# Peachy1-99-6-f.net
KiCad netlist of a schematic drawn in EAGLE
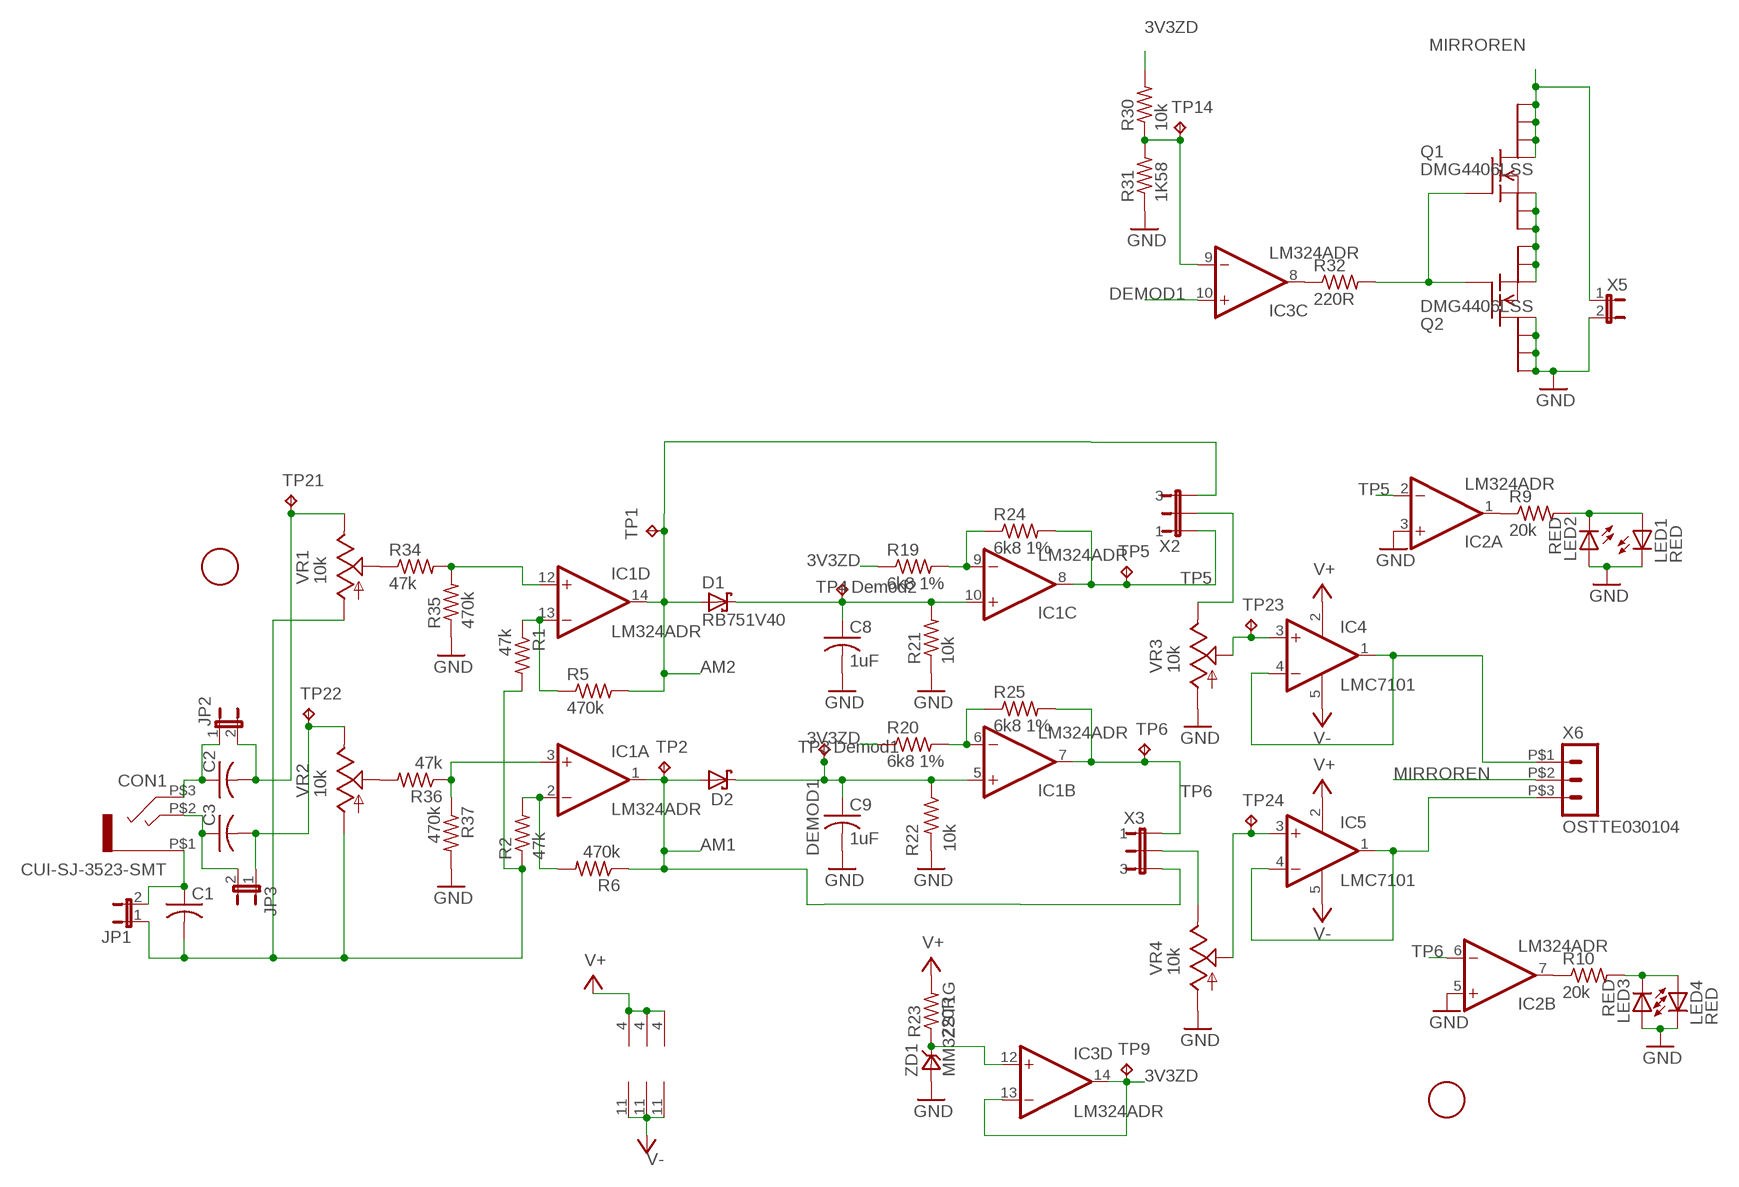
[diagram p0: schematic, sheet 1]
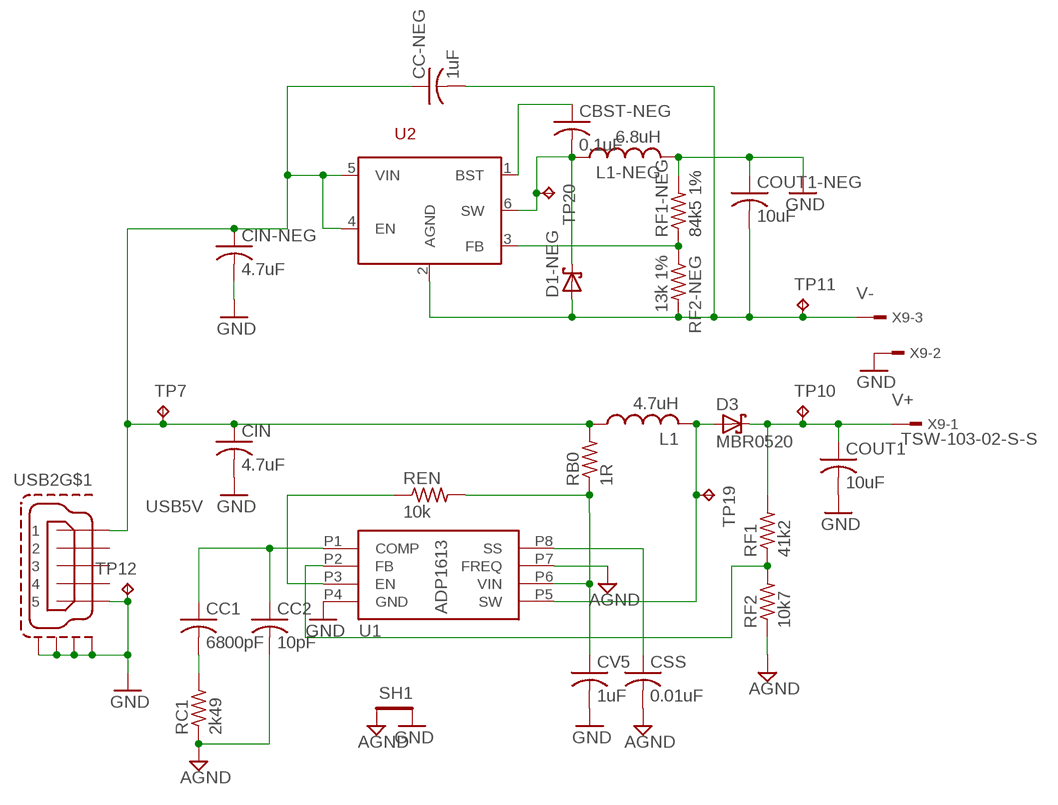
[diagram p1: schematic, sheet 2]
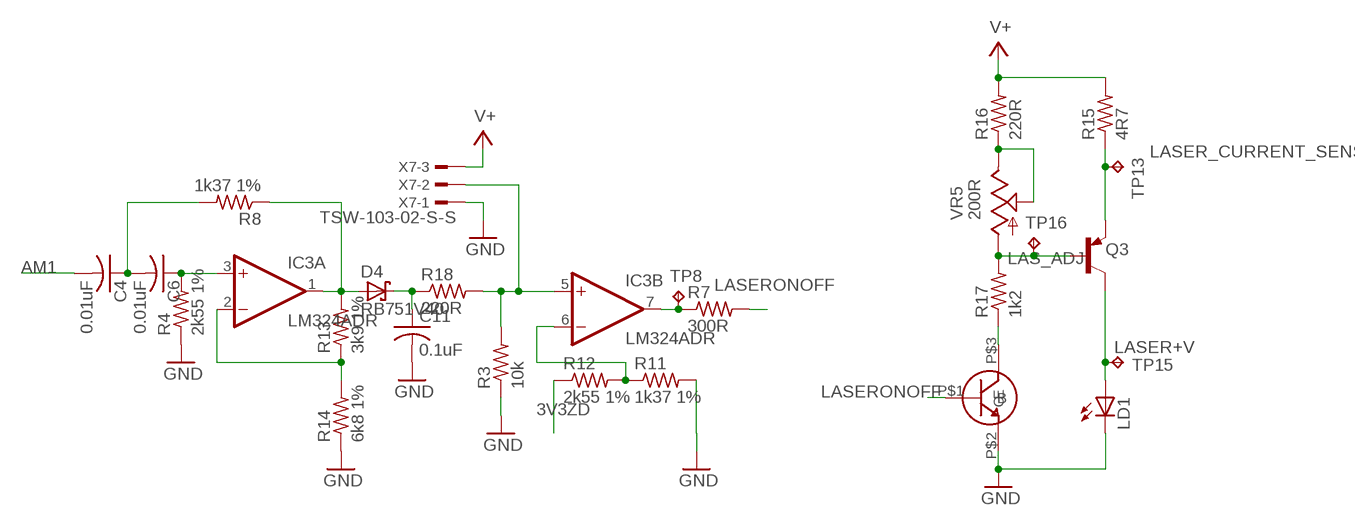
[diagram p2: schematic, sheet 3]
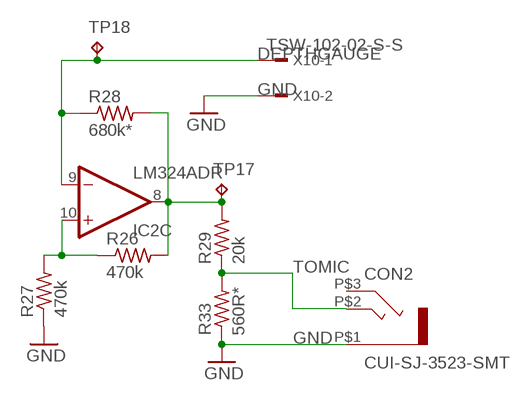
[diagram p3: schematic, sheet 4]

(export (version "E")
  (design (tool "Eeschema 10.0.6"))
  (components
    (comp (ref "C4")
      (value "0.01uF")
      (footprint "eagle-import:C0805")
      (fields (field (name "MPN") "CL21B103KBANNNC"))
      (libsource (lib "eagle-import") (part "C-US0805"))
    )
    (comp (ref "C6")
      (value "0.01uF")
      (footprint "eagle-import:C0805")
      (fields (field (name "MPN") "CL21B103KBANNNC"))
      (libsource (lib "eagle-import") (part "C-US0805"))
    )
    (comp (ref "C11")
      (value "0.1uF")
      (footprint "eagle-import:C0805")
      (fields (field (name "MPN") "CL21B104KACNNNC"))
      (libsource (lib "eagle-import") (part "C-US0805"))
    )
    (comp (ref "D4")
      (value "RB751V40")
      (footprint "eagle-import:SOD323-R")
      (fields (field (name "MPN") "RB751V40,115"))
      (libsource (lib "eagle-import") (part "RB751V40"))
    )
    (comp (ref "IC3")
      (value "LM324ADR")
      (footprint "eagle-import:SOIC14(TI-PKG-D)")
      (fields (field (name "MPN") "LM324ADR"))
      (libsource (lib "eagle-import") (part "LM324ADR"))
    )
    (comp (ref "LD1")
      (value "LASERDIODELD2")
      (footprint "eagle-import:LASERDIODE2")
      (fields (field (name "MPN") "3 x (0552-2-15-15-11-27-10-0)"))
      (libsource (lib "eagle-import") (part "LASERDIODELD2"))
    )
    (comp (ref "Q3")
      (value "BC857CT")
      (footprint "eagle-import:SC-75")
      (fields (field (name "MPN") "BC857CT,115"))
      (libsource (lib "eagle-import") (part "BC857CT"))
    )
    (comp (ref "Q4")
      (value "MMBT3904")
      (footprint "eagle-import:SOT23")
      (fields (field (name "MPN") "MMBT3904,215"))
      (libsource (lib "eagle-import") (part "MMBT3904"))
    )
    (comp (ref "R3")
      (value "10k")
      (footprint "eagle-import:R0805")
      (fields (field (name "MPN") "RMCF0805JT10K0"))
      (libsource (lib "eagle-import") (part "R-US_R0805"))
    )
    (comp (ref "R4")
      (value "2k55 1%")
      (footprint "eagle-import:R0805")
      (fields (field (name "MPN") "RC0805FR-072K55L"))
      (libsource (lib "eagle-import") (part "R-US_R0805"))
    )
    (comp (ref "R7")
      (value "300R")
      (footprint "eagle-import:R0805")
      (fields (field (name "MPN") "RC0805JR-07300RL"))
      (libsource (lib "eagle-import") (part "R-US_R0805"))
    )
    (comp (ref "R8")
      (value "1k37 1%")
      (footprint "eagle-import:R0805")
      (fields (field (name "MPN") "RC0805FR-071K37L"))
      (libsource (lib "eagle-import") (part "R-US_R0805"))
    )
    (comp (ref "R11")
      (value "1k37 1%")
      (footprint "eagle-import:R0805")
      (fields (field (name "MPN") "RC0805FR-071K37L"))
      (libsource (lib "eagle-import") (part "R-US_R0805"))
    )
    (comp (ref "R12")
      (value "2k55 1%")
      (footprint "eagle-import:R0805")
      (fields (field (name "MPN") "RC0805FR-072K55L"))
      (libsource (lib "eagle-import") (part "R-US_R0805"))
    )
    (comp (ref "R13")
      (value "3k9 1%")
      (footprint "eagle-import:R0805")
      (fields (field (name "MPN") "RC0805FR-073K9L"))
      (libsource (lib "eagle-import") (part "R-US_R0805"))
    )
    (comp (ref "R14")
      (value "6k8 1%")
      (footprint "eagle-import:R0805")
      (fields (field (name "MPN") "RC0805FR-076K8L"))
      (libsource (lib "eagle-import") (part "R-US_R0805"))
    )
    (comp (ref "R15")
      (value "4R7")
      (footprint "eagle-import:R0805")
      (fields (field (name "MPN") "RMCF0805JT4R70"))
      (libsource (lib "eagle-import") (part "R-US_R0805"))
    )
    (comp (ref "R16")
      (value "220R")
      (footprint "eagle-import:R0805")
      (fields (field (name "MPN") "RMCF0805JT220R"))
      (libsource (lib "eagle-import") (part "R-US_R0805"))
    )
    (comp (ref "R17")
      (value "1k2")
      (footprint "eagle-import:R0805")
      (fields (field (name "MPN") "RC2012J122CS"))
      (libsource (lib "eagle-import") (part "R-US_R0805"))
    )
    (comp (ref "R18")
      (value "220R")
      (footprint "eagle-import:R0805")
      (fields (field (name "MPN") "RMCF0805JT220R"))
      (libsource (lib "eagle-import") (part "R-US_R0805"))
    )
    (comp (ref "TP8")
      (value "TP017HOLE")
      (footprint "eagle-import:TP017TH")
      (libsource (lib "eagle-import") (part "TP017HOLE"))
    )
    (comp (ref "TP13")
      (value "TP017HOLE")
      (footprint "eagle-import:TP017TH")
      (fields (field (name "TP_SIGNAL_NAME") "LASER_CURRENT_SENSE"))
      (libsource (lib "eagle-import") (part "TP017HOLE"))
    )
    (comp (ref "TP15")
      (value "TP017HOLE")
      (footprint "eagle-import:TP017TH")
      (fields (field (name "TP_SIGNAL_NAME") "LASER+V"))
      (libsource (lib "eagle-import") (part "TP017HOLE"))
    )
    (comp (ref "TP16")
      (value "TP017HOLE")
      (footprint "eagle-import:TP017TH")
      (fields (field (name "TP_SIGNAL_NAME") "LAS_ADJ"))
      (libsource (lib "eagle-import") (part "TP017HOLE"))
    )
    (comp (ref "VR5")
      (value "200R")
      (footprint "eagle-import:TC33X")
      (fields (field (name "MPN") "???"))
      (libsource (lib "eagle-import") (part "TRIM_US-TC33X"))
    )
    (comp (ref "X7")
      (value "TSW-103-02-S-S")
      (footprint "eagle-import:TSW-103-02-S-S")
      (fields (field (name "MPN") "TSW-103-07-T-S"))
      (libsource (lib "eagle-import") (part "TSW-103-02-S-S"))
    )
    (comp (ref "C1")
      (value "C-US0805")
      (footprint "eagle-import:C0805")
      (libsource (lib "eagle-import") (part "C-US0805"))
    )
    (comp (ref "C2")
      (value "C-US0805")
      (footprint "eagle-import:C0805")
      (libsource (lib "eagle-import") (part "C-US0805"))
    )
    (comp (ref "C3")
      (value "C-US0805")
      (footprint "eagle-import:C0805")
      (libsource (lib "eagle-import") (part "C-US0805"))
    )
    (comp (ref "C8")
      (value "1uF")
      (footprint "eagle-import:C0805")
      (fields (field (name "MPN") "CL21B105KBFNNNE"))
      (libsource (lib "eagle-import") (part "C-US0805"))
    )
    (comp (ref "C9")
      (value "1uF")
      (footprint "eagle-import:C0805")
      (fields (field (name "MPN") "CL21B105KBFNNNE"))
      (libsource (lib "eagle-import") (part "C-US0805"))
    )
    (comp (ref "CON1")
      (value "CUI-SJ-3523-SMT")
      (footprint "eagle-import:CUI-SJ-3523-SMT")
      (fields (field (name "MPN") "SJ-3523-SMT-TR"))
      (libsource (lib "eagle-import") (part "CUI-SJ-3523-SMT"))
    )
    (comp (ref "D1")
      (value "RB751V40")
      (footprint "eagle-import:SOD323-R")
      (fields (field (name "MPN") "RB751V40,115"))
      (libsource (lib "eagle-import") (part "RB751V40"))
    )
    (comp (ref "D2")
      (value "RB751V40")
      (footprint "eagle-import:SOD323-R")
      (fields (field (name "MPN") "RB751V40,115"))
      (libsource (lib "eagle-import") (part "RB751V40"))
    )
    (comp (ref "IC1")
      (value "LM324ADR")
      (footprint "eagle-import:SOIC14(TI-PKG-D)")
      (fields (field (name "MPN") "LM324ADR"))
      (libsource (lib "eagle-import") (part "LM324ADR"))
    )
    (comp (ref "IC2")
      (value "LM324ADR")
      (footprint "eagle-import:SOIC14(TI-PKG-D)")
      (fields (field (name "MPN") "LM324ADR"))
      (libsource (lib "eagle-import") (part "LM324ADR"))
    )
    (comp (ref "IC4")
      (value "LMC7101")
      (footprint "eagle-import:SOT23-5")
      (fields (field (name "MPN") "LMC7101BYM5"))
      (libsource (lib "eagle-import") (part "LMC7101"))
    )
    (comp (ref "IC5")
      (value "LMC7101")
      (footprint "eagle-import:SOT23-5")
      (fields (field (name "MPN") "LMC7101BYM5"))
      (libsource (lib "eagle-import") (part "LMC7101"))
    )
    (comp (ref "JP1")
      (value "JUMPER-2SMD-NC")
      (footprint "eagle-import:SJ_2S")
      (libsource (lib "eagle-import") (part "JUMPER-2SMD-NC"))
    )
    (comp (ref "JP2")
      (value "JUMPER-2SMD-NC")
      (footprint "eagle-import:SJ_2S")
      (libsource (lib "eagle-import") (part "JUMPER-2SMD-NC"))
    )
    (comp (ref "JP3")
      (value "JUMPER-2SMD-NC")
      (footprint "eagle-import:SJ_2S")
      (libsource (lib "eagle-import") (part "JUMPER-2SMD-NC"))
    )
    (comp (ref "LED1")
      (value "RED")
      (footprint "eagle-import:CHIPLED_0603")
      (fields (field (name "MPN") "LS L29K-G1J2-1-Z"))
      (libsource (lib "eagle-import") (part "LEDCHIPLED_0603"))
    )
    (comp (ref "LED2")
      (value "RED")
      (footprint "eagle-import:CHIPLED_0603")
      (fields (field (name "MPN") "LS L29K-G1J2-1-Z"))
      (libsource (lib "eagle-import") (part "LEDCHIPLED_0603"))
    )
    (comp (ref "LED3")
      (value "RED")
      (footprint "eagle-import:CHIPLED_0603")
      (fields (field (name "MPN") "LS L29K-G1J2-1-Z"))
      (libsource (lib "eagle-import") (part "LEDCHIPLED_0603"))
    )
    (comp (ref "LED4")
      (value "RED")
      (footprint "eagle-import:CHIPLED_0603")
      (fields (field (name "MPN") "LS L29K-G1J2-1-Z"))
      (libsource (lib "eagle-import") (part "LEDCHIPLED_0603"))
    )
    (comp (ref "Q1")
      (value "DMG4406LSS")
      (footprint "eagle-import:SO8_DMG")
      (fields (field (name "MPN") "DMG4406LSS-13"))
      (libsource (lib "eagle-import") (part "DMG4406LSS"))
    )
    (comp (ref "Q2")
      (value "DMG4406LSS")
      (footprint "eagle-import:SO8_DMG")
      (fields (field (name "MPN") "DMG4406LSS-13"))
      (libsource (lib "eagle-import") (part "DMG4406LSS"))
    )
    (comp (ref "R1")
      (value "47k")
      (footprint "eagle-import:R0805")
      (fields (field (name "MPN") "RMCF0805JT47K0"))
      (libsource (lib "eagle-import") (part "R-US_R0805"))
    )
    (comp (ref "R2")
      (value "47k")
      (footprint "eagle-import:R0805")
      (fields (field (name "MPN") "RMCF0805JT47K0"))
      (libsource (lib "eagle-import") (part "R-US_R0805"))
    )
    (comp (ref "R5")
      (value "470k")
      (footprint "eagle-import:R0805")
      (fields (field (name "MPN") "RMCF0805JT470K"))
      (libsource (lib "eagle-import") (part "R-US_R0805"))
    )
    (comp (ref "R6")
      (value "470k")
      (footprint "eagle-import:R0805")
      (fields (field (name "MPN") "RMCF0805JT470K"))
      (libsource (lib "eagle-import") (part "R-US_R0805"))
    )
    (comp (ref "R9")
      (value "20k")
      (footprint "eagle-import:R0805")
      (fields (field (name "MPN") "RMCF0805JT20K0"))
      (libsource (lib "eagle-import") (part "R-US_R0805"))
    )
    (comp (ref "R10")
      (value "20k")
      (footprint "eagle-import:R0805")
      (fields (field (name "MPN") "RMCF0805JT20K0"))
      (libsource (lib "eagle-import") (part "R-US_R0805"))
    )
    (comp (ref "R19")
      (value "6k8 1%")
      (footprint "eagle-import:R0805")
      (fields (field (name "MPN") "RC0805FR-076K8L"))
      (libsource (lib "eagle-import") (part "R-US_R0805"))
    )
    (comp (ref "R20")
      (value "6k8 1%")
      (footprint "eagle-import:R0805")
      (fields (field (name "MPN") "RC0805FR-076K8L"))
      (libsource (lib "eagle-import") (part "R-US_R0805"))
    )
    (comp (ref "R21")
      (value "10k")
      (footprint "eagle-import:R0805")
      (fields (field (name "MPN") "RMCF0805JT10K0"))
      (libsource (lib "eagle-import") (part "R-US_R0805"))
    )
    (comp (ref "R22")
      (value "10k")
      (footprint "eagle-import:R0805")
      (fields (field (name "MPN") "RMCF0805JT10K0"))
      (libsource (lib "eagle-import") (part "R-US_R0805"))
    )
    (comp (ref "R23")
      (value "220R")
      (footprint "eagle-import:R0805")
      (fields (field (name "MPN") "RMCF0805JT220R"))
      (libsource (lib "eagle-import") (part "R-US_R0805"))
    )
    (comp (ref "R24")
      (value "6k8 1%")
      (footprint "eagle-import:R0805")
      (fields (field (name "MPN") "RC0805FR-076K8L"))
      (libsource (lib "eagle-import") (part "R-US_R0805"))
    )
    (comp (ref "R25")
      (value "6k8 1%")
      (footprint "eagle-import:R0805")
      (fields (field (name "MPN") "RC0805FR-076K8L"))
      (libsource (lib "eagle-import") (part "R-US_R0805"))
    )
    (comp (ref "R30")
      (value "10k")
      (footprint "eagle-import:R0805")
      (fields (field (name "MPN") "RMCF0805JT10K0"))
      (libsource (lib "eagle-import") (part "R-US_R0805"))
    )
    (comp (ref "R31")
      (value "1K58")
      (footprint "eagle-import:R0805")
      (fields (field (name "MPN") "RC0805FR-071K58L"))
      (libsource (lib "eagle-import") (part "R-US_R0805"))
    )
    (comp (ref "R32")
      (value "220R")
      (footprint "eagle-import:R0805")
      (fields (field (name "MPN") "RMCF0805JT220R"))
      (libsource (lib "eagle-import") (part "R-US_R0805"))
    )
    (comp (ref "R34")
      (value "47k")
      (footprint "eagle-import:R0805")
      (fields (field (name "MPN") "RMCF0805JT47K0"))
      (libsource (lib "eagle-import") (part "R-US_R0805"))
    )
    (comp (ref "R35")
      (value "470k")
      (footprint "eagle-import:R0805")
      (fields (field (name "MPN") "RMCF0805JT470K"))
      (libsource (lib "eagle-import") (part "R-US_R0805"))
    )
    (comp (ref "R36")
      (value "47k")
      (footprint "eagle-import:R0805")
      (fields (field (name "MPN") "RMCF0805JT47K0"))
      (libsource (lib "eagle-import") (part "R-US_R0805"))
    )
    (comp (ref "R37")
      (value "470k")
      (footprint "eagle-import:R0805")
      (fields (field (name "MPN") "RMCF0805JT470K"))
      (libsource (lib "eagle-import") (part "R-US_R0805"))
    )
    (comp (ref "TP1")
      (value "TP017HOLE")
      (footprint "eagle-import:TP017TH")
      (fields (field (name "TP_SIGNAL_NAME") "Preamp2"))
      (libsource (lib "eagle-import") (part "TP017HOLE"))
    )
    (comp (ref "TP2")
      (value "TP017HOLE")
      (footprint "eagle-import:TP017TH")
      (fields (field (name "TP_SIGNAL_NAME") "Preamp1"))
      (libsource (lib "eagle-import") (part "TP017HOLE"))
    )
    (comp (ref "TP3")
      (value "TP017HOLE")
      (footprint "eagle-import:TP017TH")
      (fields (field (name "TP_SIGNAL_NAME") "Demod1"))
      (libsource (lib "eagle-import") (part "TP017HOLE"))
    )
    (comp (ref "TP4")
      (value "TP017HOLE")
      (footprint "eagle-import:TP017TH")
      (fields (field (name "TP_SIGNAL_NAME") "Demod2"))
      (libsource (lib "eagle-import") (part "TP017HOLE"))
    )
    (comp (ref "TP5")
      (value "TP017HOLE")
      (footprint "eagle-import:TP017TH")
      (fields (field (name "TP_SIGNAL_NAME") "TP5"))
      (libsource (lib "eagle-import") (part "TP017HOLE"))
    )
    (comp (ref "TP6")
      (value "TP017HOLE")
      (footprint "eagle-import:TP017TH")
      (fields (field (name "TP_SIGNAL_NAME") "TP6"))
      (libsource (lib "eagle-import") (part "TP017HOLE"))
    )
    (comp (ref "TP9")
      (value "TP017HOLE")
      (footprint "eagle-import:TP017TH")
      (libsource (lib "eagle-import") (part "TP017HOLE"))
    )
    (comp (ref "TP14")
      (value "TP017HOLE")
      (footprint "eagle-import:TP017TH")
      (libsource (lib "eagle-import") (part "TP017HOLE"))
    )
    (comp (ref "TP21")
      (value "TP017HOLE")
      (footprint "eagle-import:TP017TH")
      (libsource (lib "eagle-import") (part "TP017HOLE"))
    )
    (comp (ref "TP22")
      (value "TP017HOLE")
      (footprint "eagle-import:TP017TH")
      (libsource (lib "eagle-import") (part "TP017HOLE"))
    )
    (comp (ref "TP23")
      (value "TP017HOLE")
      (footprint "eagle-import:TP017TH")
      (libsource (lib "eagle-import") (part "TP017HOLE"))
    )
    (comp (ref "TP24")
      (value "TP017HOLE")
      (footprint "eagle-import:TP017TH")
      (libsource (lib "eagle-import") (part "TP017HOLE"))
    )
    (comp (ref "U$2")
      (value "FIDUCIAL")
      (footprint "eagle-import:FIDUCIAL_1MM")
      (libsource (lib "eagle-import") (part "FIDUCIAL"))
    )
    (comp (ref "U$3")
      (value "FIDUCIAL")
      (footprint "eagle-import:FIDUCIAL_1MM")
      (libsource (lib "eagle-import") (part "FIDUCIAL"))
    )
    (comp (ref "VR1")
      (value "10k")
      (footprint "eagle-import:67W")
      (fields (field (name "MPN") "67WR10KLF"))
      (libsource (lib "eagle-import") (part "TRIM_US-67W"))
    )
    (comp (ref "VR2")
      (value "10k")
      (footprint "eagle-import:67W")
      (fields (field (name "MPN") "67WR10KLF"))
      (libsource (lib "eagle-import") (part "TRIM_US-67W"))
    )
    (comp (ref "VR3")
      (value "10k")
      (footprint "eagle-import:PVZ3A")
      (fields (field (name "MPN") "PVZ3A103C01R00"))
      (libsource (lib "eagle-import") (part "TRIM_US-PVZ3A"))
    )
    (comp (ref "VR4")
      (value "10k")
      (footprint "eagle-import:PVZ3A")
      (fields (field (name "MPN") "PVZ3A103C01R00"))
      (libsource (lib "eagle-import") (part "TRIM_US-PVZ3A"))
    )
    (comp (ref "X2")
      (value "JUMPER-31-2")
      (footprint "eagle-import:SJ_3_PASTE1&2")
      (libsource (lib "eagle-import") (part "JUMPER-31-2"))
    )
    (comp (ref "X3")
      (value "JUMPER-31-2")
      (footprint "eagle-import:SJ_3_PASTE1&2")
      (libsource (lib "eagle-import") (part "JUMPER-31-2"))
    )
    (comp (ref "X5")
      (value "JUMPER-2SMD-NO")
      (footprint "eagle-import:SJ_2S-NO")
      (libsource (lib "eagle-import") (part "JUMPER-2SMD-NO"))
    )
    (comp (ref "X6")
      (value "OSTTE030104")
      (footprint "eagle-import:OSTTE030104")
      (libsource (lib "eagle-import") (part "OSTTE030104"))
    )
    (comp (ref "ZD1")
      (value "MM3ZST1G")
      (footprint "eagle-import:SOD323-R")
      (fields (field (name "MPN") "BZX384-B3V3,115"))
      (libsource (lib "eagle-import") (part "MM3ZST1G"))
    )
    (comp (ref "CBST-NEG")
      (value "0.1uF")
      (footprint "eagle-import:C0805")
      (fields (field (name "MPN") "CL21B104KACNNNC"))
      (libsource (lib "eagle-import") (part "C-US0805"))
    )
    (comp (ref "CC-NEG")
      (value "1uF")
      (footprint "eagle-import:C0805")
      (fields (field (name "MPN") "CL21B105KBFNNNE"))
      (libsource (lib "eagle-import") (part "C-US0805"))
    )
    (comp (ref "CC1")
      (value "6800pF")
      (footprint "eagle-import:C0805")
      (fields (field (name "MPN") "CL21B682KBANNNC"))
      (libsource (lib "eagle-import") (part "C-US0805"))
    )
    (comp (ref "CC2")
      (value "10pF")
      (footprint "eagle-import:C0805")
      (fields (field (name "MPN") "CL21C100JCANNNC"))
      (libsource (lib "eagle-import") (part "C-US0805"))
    )
    (comp (ref "CIN")
      (value "4.7uF")
      (footprint "eagle-import:C0805")
      (fields (field (name "MPN") "CL21A475KOFNNNE"))
      (libsource (lib "eagle-import") (part "C-US0805"))
    )
    (comp (ref "CIN-NEG")
      (value "4.7uF")
      (footprint "eagle-import:C0805")
      (fields (field (name "MPN") "CL21A475KOFNNNE"))
      (libsource (lib "eagle-import") (part "C-US0805"))
    )
    (comp (ref "COUT1")
      (value "10uF")
      (footprint "eagle-import:C0805")
      (fields (field (name "MPN") "CL21B106KQQNNNE"))
      (libsource (lib "eagle-import") (part "C-US0805"))
    )
    (comp (ref "COUT1-NEG")
      (value "10uF")
      (footprint "eagle-import:C0805")
      (fields (field (name "MPN") "CL21B106KQQNNNE"))
      (libsource (lib "eagle-import") (part "C-US0805"))
    )
    (comp (ref "CSS")
      (value "0.01uF")
      (footprint "eagle-import:C0805")
      (fields (field (name "MPN") "CL21B103KBANNNC"))
      (libsource (lib "eagle-import") (part "C-US0805"))
    )
    (comp (ref "CV5")
      (value "1uF")
      (footprint "eagle-import:C0805")
      (fields (field (name "MPN") "CL21B105KBFNNNE"))
      (libsource (lib "eagle-import") (part "C-US0805"))
    )
    (comp (ref "D1-NEG")
      (value "MBR0520")
      (footprint "eagle-import:SOD123")
      (fields (field (name "MPN") "MBR0520LT3G"))
      (libsource (lib "eagle-import") (part "SCHOTTKYSOD123"))
    )
    (comp (ref "D3")
      (value "MBR0520")
      (footprint "eagle-import:SOD123")
      (fields (field (name "MPN") "MBR0520LT3G"))
      (libsource (lib "eagle-import") (part "SCHOTTKYSOD123"))
    )
    (comp (ref "L1")
      (value "4.7uH")
      (footprint "eagle-import:L1210")
      (fields (field (name "MPN") "LQH32PN4R7NN0L"))
      (libsource (lib "eagle-import") (part "L-USL1210"))
    )
    (comp (ref "L1-NEG")
      (value "6.8uH")
      (footprint "eagle-import:L1210")
      (fields (field (name "MPN") "LQH32PN6R8NN0"))
      (libsource (lib "eagle-import") (part "L-USL1210"))
    )
    (comp (ref "RB0")
      (value "1R")
      (footprint "eagle-import:R0805")
      (fields (field (name "MPN") "RMCF0805JT1R00 "))
      (libsource (lib "eagle-import") (part "R-US_R0805"))
    )
    (comp (ref "RC1")
      (value "2k49")
      (footprint "eagle-import:R0805")
      (fields (field (name "MPN") "RMCF0805FT2K49"))
      (libsource (lib "eagle-import") (part "R-US_R0805"))
    )
    (comp (ref "REN")
      (value "10k")
      (footprint "eagle-import:R0805")
      (fields (field (name "MPN") "RMCF0805JT10K0"))
      (libsource (lib "eagle-import") (part "R-US_R0805"))
    )
    (comp (ref "RF1")
      (value "41k2")
      (footprint "eagle-import:R0805")
      (fields (field (name "MPN") "RC0805FR-0741K2L"))
      (libsource (lib "eagle-import") (part "R-US_R0805"))
    )
    (comp (ref "RF1-NEG")
      (value "84k5 1%")
      (footprint "eagle-import:R0805")
      (fields (field (name "MPN") "RC0805FR-0784K5L"))
      (libsource (lib "eagle-import") (part "R-US_R0805"))
    )
    (comp (ref "RF2")
      (value "10k7")
      (footprint "eagle-import:R0805")
      (fields (field (name "MPN") "RC2012F1072CS"))
      (libsource (lib "eagle-import") (part "R-US_R0805"))
    )
    (comp (ref "RF2-NEG")
      (value "13k 1%")
      (footprint "eagle-import:R0805")
      (fields (field (name "MPN") "RC0805FR-0713KL"))
      (libsource (lib "eagle-import") (part "R-US_R0805"))
    )
    (comp (ref "SH1")
      (value "SHORT-HT5")
      (footprint "eagle-import:SHORT_TOP-50")
      (libsource (lib "eagle-import") (part "SHORT-HT5"))
    )
    (comp (ref "TP7")
      (value "TP017HOLE")
      (footprint "eagle-import:TP017TH")
      (libsource (lib "eagle-import") (part "TP017HOLE"))
    )
    (comp (ref "TP10")
      (value "TP017HOLE")
      (footprint "eagle-import:TP017TH")
      (fields (field (name "TP_SIGNAL_NAME") "+V"))
      (libsource (lib "eagle-import") (part "TP017HOLE"))
    )
    (comp (ref "TP11")
      (value "TP017HOLE")
      (footprint "eagle-import:TP017TH")
      (fields (field (name "TP_SIGNAL_NAME") "V-"))
      (libsource (lib "eagle-import") (part "TP017HOLE"))
    )
    (comp (ref "TP12")
      (value "TP017HOLE")
      (footprint "eagle-import:TP017TH")
      (libsource (lib "eagle-import") (part "TP017HOLE"))
    )
    (comp (ref "TP19")
      (value "TP017HOLE")
      (footprint "eagle-import:TP017TH")
      (fields (field (name "TP_SIGNAL_NAME") "SW+"))
      (libsource (lib "eagle-import") (part "TP017HOLE"))
    )
    (comp (ref "TP20")
      (value "TP017HOLE")
      (footprint "eagle-import:TP017TH")
      (libsource (lib "eagle-import") (part "TP017HOLE"))
    )
    (comp (ref "U1")
      (value "ADP1613")
      (footprint "eagle-import:RM-8")
      (fields (field (name "MPN") "ADP1613ARMZ-R7"))
      (libsource (lib "eagle-import") (part "ADP1613"))
    )
    (comp (ref "U2")
      (value "ADP2300")
      (footprint "eagle-import:TSOT23-6")
      (fields (field (name "MPN") "ADP2300AUJZ-R7"))
      (libsource (lib "eagle-import") (part "ADP2300"))
    )
    (comp (ref "USB2")
      (value "FCI-MICROUSBAPCIRCUITS")
      (footprint "eagle-import:FCI-USB-10118193-APCIRCUITS")
      (fields (field (name "MPN") "10118193-0001LF"))
      (libsource (lib "eagle-import") (part "FCI-MICROUSBAPCIRCUITS"))
    )
    (comp (ref "X9")
      (value "TSW-103-02-S-S")
      (footprint "eagle-import:TSW-103-02-S-S")
      (fields (field (name "MPN") "TSW-103-07-T-S"))
      (libsource (lib "eagle-import") (part "TSW-103-02-S-S"))
    )
    (comp (ref "CON2")
      (value "CUI-SJ-3523-SMT")
      (footprint "eagle-import:CUI-SJ-3523-SMT")
      (fields (field (name "MPN") "SJ-3523-SMT-TR"))
      (libsource (lib "eagle-import") (part "CUI-SJ-3523-SMT"))
    )
    (comp (ref "R26")
      (value "470k")
      (footprint "eagle-import:R0805")
      (fields (field (name "MPN") "RMCF0805JT470K"))
      (libsource (lib "eagle-import") (part "R-US_R0805"))
    )
    (comp (ref "R27")
      (value "470k")
      (footprint "eagle-import:R0805")
      (fields (field (name "MPN") "RMCF0805JT470K"))
      (libsource (lib "eagle-import") (part "R-US_R0805"))
    )
    (comp (ref "R28")
      (value "680k*")
      (footprint "eagle-import:70543-02")
      (fields (field (name "MPN") "PPTC021LFBN-RC"))
      (libsource (lib "eagle-import") (part "R-US_SOCKET(.1)"))
    )
    (comp (ref "R29")
      (value "20k")
      (footprint "eagle-import:R0805")
      (fields (field (name "MPN") "RMCF0805JT20K0"))
      (libsource (lib "eagle-import") (part "R-US_R0805"))
    )
    (comp (ref "R33")
      (value "560R*")
      (footprint "eagle-import:R0805")
      (fields (field (name "MPN") "RMCF0805JT560R"))
      (libsource (lib "eagle-import") (part "R-US_R0805"))
    )
    (comp (ref "TP17")
      (value "TP017HOLE")
      (footprint "eagle-import:TP017TH")
      (libsource (lib "eagle-import") (part "TP017HOLE"))
    )
    (comp (ref "TP18")
      (value "TP017HOLE")
      (footprint "eagle-import:TP017TH")
      (libsource (lib "eagle-import") (part "TP017HOLE"))
    )
    (comp (ref "X10")
      (value "TSW-102-02-S-S")
      (footprint "eagle-import:TSW-102-02-S-S")
      (libsource (lib "eagle-import") (part "TSW-102-02-S-S"))
    )
  )
  (nets
    (net (code "1") (name "3V3ZD") (class "Default")
      (node (ref "IC3") (pin "13") (pinfunction "-IN_13") (pintype "input"))
      (node (ref "IC3") (pin "14") (pinfunction "OUT_14") (pintype "output"))
      (node (ref "R12") (pin "1") (pinfunction "1_1") (pintype "passive"))
      (node (ref "R19") (pin "1") (pinfunction "1_1") (pintype "passive"))
      (node (ref "R20") (pin "1") (pinfunction "1_1") (pintype "passive"))
      (node (ref "R30") (pin "2") (pinfunction "2_2") (pintype "passive"))
      (node (ref "TP9") (pin "P$1") (pinfunction "TP_P$1") (pintype "input"))
    )
    (net (code "2") (name "AGND") (class "Default")
      (node (ref "CC2") (pin "2") (pinfunction "2_2") (pintype "passive"))
      (node (ref "CSS") (pin "2") (pinfunction "2_2") (pintype "passive"))
      (node (ref "RC1") (pin "1") (pinfunction "1_1") (pintype "passive"))
      (node (ref "RF2") (pin "1") (pinfunction "1_1") (pintype "passive"))
      (node (ref "SH1") (pin "1") (pinfunction "P$1_1") (pintype "bidirectional"))
      (node (ref "U1") (pin "P7") (pinfunction "FREQ_P7") (pintype "bidirectional"))
    )
    (net (code "3") (name "AM1") (class "Default")
      (node (ref "C4") (pin "2") (pinfunction "2_2") (pintype "passive"))
      (node (ref "D2") (pin "A") (pinfunction "A_A") (pintype "passive"))
      (node (ref "IC1") (pin "1") (pinfunction "OUT_1") (pintype "output"))
      (node (ref "R6") (pin "1") (pinfunction "1_1") (pintype "passive"))
      (node (ref "TP2") (pin "P$1") (pinfunction "TP_P$1") (pintype "input"))
      (node (ref "X3") (pin "3") (pinfunction "3_3") (pintype "passive"))
    )
    (net (code "4") (name "AM2") (class "Default")
      (node (ref "D1") (pin "A") (pinfunction "A_A") (pintype "passive"))
      (node (ref "IC1") (pin "14") (pinfunction "OUT_14") (pintype "output"))
      (node (ref "R5") (pin "2") (pinfunction "2_2") (pintype "passive"))
      (node (ref "TP1") (pin "P$1") (pinfunction "TP_P$1") (pintype "input"))
      (node (ref "X2") (pin "3") (pinfunction "3_3") (pintype "passive"))
    )
    (net (code "5") (name "DEMOD1") (class "Default")
      (node (ref "C9") (pin "1") (pinfunction "1_1") (pintype "passive"))
      (node (ref "D2") (pin "C") (pinfunction "C_C") (pintype "passive"))
      (node (ref "IC1") (pin "5") (pinfunction "+IN_5") (pintype "input"))
      (node (ref "IC3") (pin "10") (pinfunction "+IN_10") (pintype "input"))
      (node (ref "R22") (pin "1") (pinfunction "1_1") (pintype "passive"))
      (node (ref "TP3") (pin "P$1") (pinfunction "TP_P$1") (pintype "input"))
    )
    (net (code "6") (name "DEPTHGAUGE") (class "Default")
      (node (ref "IC2") (pin "9") (pinfunction "-IN_9") (pintype "input"))
      (node (ref "R28") (pin "1") (pinfunction "1_1") (pintype "passive"))
      (node (ref "TP18") (pin "P$1") (pinfunction "TP_P$1") (pintype "input"))
      (node (ref "X10") (pin "1") (pinfunction "1_1") (pintype "passive"))
    )
    (net (code "7") (name "GND") (class "Default")
      (node (ref "C11") (pin "2") (pinfunction "2_2") (pintype "passive"))
      (node (ref "C8") (pin "2") (pinfunction "2_2") (pintype "passive"))
      (node (ref "C9") (pin "2") (pinfunction "2_2") (pintype "passive"))
      (node (ref "CIN") (pin "2") (pinfunction "2_2") (pintype "passive"))
      (node (ref "CIN-NEG") (pin "2") (pinfunction "2_2") (pintype "passive"))
      (node (ref "CON2") (pin "P$1") (pinfunction "1_P$1") (pintype "passive"))
      (node (ref "COUT1") (pin "2") (pinfunction "2_2") (pintype "passive"))
      (node (ref "COUT1-NEG") (pin "1") (pinfunction "1_1") (pintype "passive"))
      (node (ref "CV5") (pin "2") (pinfunction "2_2") (pintype "passive"))
      (node (ref "IC2") (pin "3") (pinfunction "+IN_3") (pintype "input"))
      (node (ref "IC2") (pin "5") (pinfunction "+IN_5") (pintype "input"))
      (node (ref "L1-NEG") (pin "2") (pinfunction "2_2") (pintype "passive"))
      (node (ref "LD1") (pin "P$3") (pinfunction "C_P$3") (pintype "passive"))
      (node (ref "LED1") (pin "C") (pinfunction "C_C") (pintype "passive"))
      (node (ref "LED2") (pin "A") (pinfunction "A_A") (pintype "passive"))
      (node (ref "LED3") (pin "A") (pinfunction "A_A") (pintype "passive"))
      (node (ref "LED4") (pin "C") (pinfunction "C_C") (pintype "passive"))
      (node (ref "Q2") (pin "P$5") (pinfunction "D_P$5") (pintype "passive"))
      (node (ref "Q2") (pin "P$6") (pinfunction "D_P$6") (pintype "passive"))
      (node (ref "Q2") (pin "P$7") (pinfunction "D_P$7") (pintype "passive"))
      (node (ref "Q2") (pin "P$8") (pinfunction "D_P$8") (pintype "passive"))
      (node (ref "Q4") (pin "P$2") (pinfunction "E_P$2") (pintype "input"))
      (node (ref "R11") (pin "2") (pinfunction "2_2") (pintype "passive"))
      (node (ref "R14") (pin "1") (pinfunction "1_1") (pintype "passive"))
      (node (ref "R21") (pin "1") (pinfunction "1_1") (pintype "passive"))
      (node (ref "R22") (pin "2") (pinfunction "2_2") (pintype "passive"))
      (node (ref "R27") (pin "1") (pinfunction "1_1") (pintype "passive"))
      (node (ref "R3") (pin "1") (pinfunction "1_1") (pintype "passive"))
      (node (ref "R31") (pin "1") (pinfunction "1_1") (pintype "passive"))
      (node (ref "R33") (pin "1") (pinfunction "1_1") (pintype "passive"))
      (node (ref "R35") (pin "1") (pinfunction "1_1") (pintype "passive"))
      (node (ref "R37") (pin "2") (pinfunction "2_2") (pintype "passive"))
      (node (ref "R4") (pin "1") (pinfunction "1_1") (pintype "passive"))
      (node (ref "RF1-NEG") (pin "2") (pinfunction "2_2") (pintype "passive"))
      (node (ref "SH1") (pin "2") (pinfunction "P$2_2") (pintype "bidirectional"))
      (node (ref "TP12") (pin "P$1") (pinfunction "TP_P$1") (pintype "input"))
      (node (ref "U1") (pin "P4") (pinfunction "GND_P4") (pintype "bidirectional"))
      (node (ref "USB2") (pin "P$11") (pinfunction "S4_P$11") (pintype "passive"))
      (node (ref "USB2") (pin "P$5") (pinfunction "5_P$5") (pintype "input"))
      (node (ref "USB2") (pin "P$6") (pinfunction "S1_P$6") (pintype "passive"))
      (node (ref "USB2") (pin "P$7") (pinfunction "S2_P$7") (pintype "passive"))
      (node (ref "USB2") (pin "P$8") (pinfunction "S3_P$8") (pintype "passive"))
      (node (ref "VR3") (pin "P$1") (pinfunction "A_P$1") (pintype "passive"))
      (node (ref "VR4") (pin "P$1") (pinfunction "A_P$1") (pintype "passive"))
      (node (ref "X10") (pin "2") (pinfunction "1_2") (pintype "passive"))
      (node (ref "X5") (pin "2") (pinfunction "2_2") (pintype "passive"))
      (node (ref "X7") (pin "1") (pinfunction "1_1") (pintype "passive"))
      (node (ref "X9") (pin "2") (pinfunction "1_2") (pintype "passive"))
      (node (ref "ZD1") (pin "A") (pinfunction "A_A") (pintype "passive"))
    )
    (net (code "8") (name "LASERONOFF") (class "Default")
      (node (ref "Q4") (pin "P$1") (pinfunction "B_P$1") (pintype "input"))
      (node (ref "R7") (pin "2") (pinfunction "2_2") (pintype "passive"))
    )
    (net (code "9") (name "MIRROREN") (class "Default")
      (node (ref "Q1") (pin "P$5") (pinfunction "D_P$5") (pintype "passive"))
      (node (ref "Q1") (pin "P$6") (pinfunction "D_P$6") (pintype "passive"))
      (node (ref "Q1") (pin "P$7") (pinfunction "D_P$7") (pintype "passive"))
      (node (ref "Q1") (pin "P$8") (pinfunction "D_P$8") (pintype "passive"))
      (node (ref "X5") (pin "1") (pinfunction "1_1") (pintype "passive"))
      (node (ref "X6") (pin "P$2") (pinfunction "2_P$2") (pintype "passive"))
    )
    (net (code "10") (name "Net-(C1-Pad2)") (class "Default")
      (node (ref "C1") (pin "2") (pinfunction "2_2") (pintype "passive"))
      (node (ref "JP1") (pin "1") (pinfunction "1_1") (pintype "passive"))
      (node (ref "R1") (pin "2") (pinfunction "2_2") (pintype "passive"))
      (node (ref "R2") (pin "1") (pinfunction "1_1") (pintype "passive"))
      (node (ref "VR1") (pin "A") (pinfunction "A_A") (pintype "passive"))
      (node (ref "VR2") (pin "A") (pinfunction "A_A") (pintype "passive"))
    )
    (net (code "11") (name "Net-(C4-Pad1)") (class "Default")
      (node (ref "C4") (pin "1") (pinfunction "1_1") (pintype "passive"))
      (node (ref "C6") (pin "2") (pinfunction "2_2") (pintype "passive"))
      (node (ref "R8") (pin "2") (pinfunction "2_2") (pintype "passive"))
    )
    (net (code "12") (name "Net-(C11-Pad1)") (class "Default")
      (node (ref "C11") (pin "1") (pinfunction "1_1") (pintype "passive"))
      (node (ref "D4") (pin "C") (pinfunction "C_C") (pintype "passive"))
      (node (ref "R18") (pin "1") (pinfunction "1_1") (pintype "passive"))
    )
    (net (code "13") (name "Net-(CC1-Pad2)") (class "Default")
      (node (ref "CC1") (pin "2") (pinfunction "2_2") (pintype "passive"))
      (node (ref "RC1") (pin "2") (pinfunction "2_2") (pintype "passive"))
    )
    (net (code "14") (name "Net-(CON1-1)") (class "Default")
      (node (ref "C1") (pin "1") (pinfunction "1_1") (pintype "passive"))
      (node (ref "CON1") (pin "P$1") (pinfunction "1_P$1") (pintype "passive"))
      (node (ref "JP1") (pin "2") (pinfunction "2_2") (pintype "passive"))
    )
    (net (code "15") (name "Net-(CON1-2)") (class "Default")
      (node (ref "C2") (pin "1") (pinfunction "1_1") (pintype "passive"))
      (node (ref "CON1") (pin "P$3") (pinfunction "2_P$3") (pintype "passive"))
      (node (ref "JP2") (pin "1") (pinfunction "1_1") (pintype "passive"))
    )
    (net (code "16") (name "Net-(CON1-3)") (class "Default")
      (node (ref "C3") (pin "1") (pinfunction "1_1") (pintype "passive"))
      (node (ref "CON1") (pin "P$2") (pinfunction "3_P$2") (pintype "passive"))
      (node (ref "JP3") (pin "2") (pinfunction "2_2") (pintype "passive"))
    )
    (net (code "17") (name "Net-(IC1A-+IN)") (class "Default")
      (node (ref "IC1") (pin "3") (pinfunction "+IN_3") (pintype "input"))
      (node (ref "R36") (pin "1") (pinfunction "1_1") (pintype "passive"))
      (node (ref "R37") (pin "1") (pinfunction "1_1") (pintype "passive"))
    )
    (net (code "18") (name "Net-(IC1A--IN)") (class "Default")
      (node (ref "IC1") (pin "2") (pinfunction "-IN_2") (pintype "input"))
      (node (ref "R2") (pin "2") (pinfunction "2_2") (pintype "passive"))
      (node (ref "R6") (pin "2") (pinfunction "2_2") (pintype "passive"))
    )
    (net (code "19") (name "Net-(IC1B--IN)") (class "Default")
      (node (ref "IC1") (pin "6") (pinfunction "-IN_6") (pintype "input"))
      (node (ref "R20") (pin "2") (pinfunction "2_2") (pintype "passive"))
      (node (ref "R25") (pin "1") (pinfunction "1_1") (pintype "passive"))
    )
    (net (code "20") (name "Net-(IC1C-+IN)") (class "Default")
      (node (ref "C8") (pin "1") (pinfunction "1_1") (pintype "passive"))
      (node (ref "D1") (pin "C") (pinfunction "C_C") (pintype "passive"))
      (node (ref "IC1") (pin "10") (pinfunction "+IN_10") (pintype "input"))
      (node (ref "R21") (pin "2") (pinfunction "2_2") (pintype "passive"))
      (node (ref "TP4") (pin "P$1") (pinfunction "TP_P$1") (pintype "input"))
    )
    (net (code "21") (name "Net-(IC1C--IN)") (class "Default")
      (node (ref "IC1") (pin "9") (pinfunction "-IN_9") (pintype "input"))
      (node (ref "R19") (pin "2") (pinfunction "2_2") (pintype "passive"))
      (node (ref "R24") (pin "1") (pinfunction "1_1") (pintype "passive"))
    )
    (net (code "22") (name "Net-(IC1D-+IN)") (class "Default")
      (node (ref "IC1") (pin "12") (pinfunction "+IN_12") (pintype "input"))
      (node (ref "R34") (pin "2") (pinfunction "2_2") (pintype "passive"))
      (node (ref "R35") (pin "2") (pinfunction "2_2") (pintype "passive"))
    )
    (net (code "23") (name "Net-(IC1D--IN)") (class "Default")
      (node (ref "IC1") (pin "13") (pinfunction "-IN_13") (pintype "input"))
      (node (ref "R1") (pin "1") (pinfunction "1_1") (pintype "passive"))
      (node (ref "R5") (pin "1") (pinfunction "1_1") (pintype "passive"))
    )
    (net (code "24") (name "Net-(IC2A-OUT)") (class "Default")
      (node (ref "IC2") (pin "1") (pinfunction "OUT_1") (pintype "output"))
      (node (ref "R9") (pin "1") (pinfunction "1_1") (pintype "passive"))
    )
    (net (code "25") (name "Net-(IC2B-OUT)") (class "Default")
      (node (ref "IC2") (pin "7") (pinfunction "OUT_7") (pintype "output"))
      (node (ref "R10") (pin "1") (pinfunction "1_1") (pintype "passive"))
    )
    (net (code "26") (name "Net-(IC2C-+IN)") (class "Default")
      (node (ref "IC2") (pin "10") (pinfunction "+IN_10") (pintype "input"))
      (node (ref "R26") (pin "1") (pinfunction "1_1") (pintype "passive"))
      (node (ref "R27") (pin "2") (pinfunction "2_2") (pintype "passive"))
    )
    (net (code "27") (name "Net-(IC2C-OUT)") (class "Default")
      (node (ref "IC2") (pin "8") (pinfunction "OUT_8") (pintype "output"))
      (node (ref "R26") (pin "2") (pinfunction "2_2") (pintype "passive"))
      (node (ref "R28") (pin "2") (pinfunction "2_2") (pintype "passive"))
      (node (ref "R29") (pin "2") (pinfunction "2_2") (pintype "passive"))
      (node (ref "TP17") (pin "P$1") (pinfunction "TP_P$1") (pintype "input"))
    )
    (net (code "28") (name "Net-(IC3A-+IN)") (class "Default")
      (node (ref "C6") (pin "1") (pinfunction "1_1") (pintype "passive"))
      (node (ref "IC3") (pin "3") (pinfunction "+IN_3") (pintype "input"))
      (node (ref "R4") (pin "2") (pinfunction "2_2") (pintype "passive"))
    )
    (net (code "29") (name "Net-(IC3A--IN)") (class "Default")
      (node (ref "IC3") (pin "2") (pinfunction "-IN_2") (pintype "input"))
      (node (ref "R13") (pin "1") (pinfunction "1_1") (pintype "passive"))
      (node (ref "R14") (pin "2") (pinfunction "2_2") (pintype "passive"))
    )
    (net (code "30") (name "Net-(IC3A-OUT)") (class "Default")
      (node (ref "D4") (pin "A") (pinfunction "A_A") (pintype "passive"))
      (node (ref "IC3") (pin "1") (pinfunction "OUT_1") (pintype "output"))
      (node (ref "R13") (pin "2") (pinfunction "2_2") (pintype "passive"))
      (node (ref "R8") (pin "1") (pinfunction "1_1") (pintype "passive"))
    )
    (net (code "31") (name "Net-(IC3B-+IN)") (class "Default")
      (node (ref "IC3") (pin "5") (pinfunction "+IN_5") (pintype "input"))
      (node (ref "R18") (pin "2") (pinfunction "2_2") (pintype "passive"))
      (node (ref "R3") (pin "2") (pinfunction "2_2") (pintype "passive"))
      (node (ref "X7") (pin "2") (pinfunction "1_2") (pintype "passive"))
    )
    (net (code "32") (name "Net-(IC3B--IN)") (class "Default")
      (node (ref "IC3") (pin "6") (pinfunction "-IN_6") (pintype "input"))
      (node (ref "R11") (pin "1") (pinfunction "1_1") (pintype "passive"))
      (node (ref "R12") (pin "2") (pinfunction "2_2") (pintype "passive"))
    )
    (net (code "33") (name "Net-(IC3B-OUT)") (class "Default")
      (node (ref "IC3") (pin "7") (pinfunction "OUT_7") (pintype "output"))
      (node (ref "R7") (pin "1") (pinfunction "1_1") (pintype "passive"))
      (node (ref "TP8") (pin "P$1") (pinfunction "TP_P$1") (pintype "input"))
    )
    (net (code "34") (name "Net-(IC3C--IN)") (class "Default")
      (node (ref "IC3") (pin "9") (pinfunction "-IN_9") (pintype "input"))
      (node (ref "R30") (pin "1") (pinfunction "1_1") (pintype "passive"))
      (node (ref "R31") (pin "2") (pinfunction "2_2") (pintype "passive"))
      (node (ref "TP14") (pin "P$1") (pinfunction "TP_P$1") (pintype "input"))
    )
    (net (code "35") (name "Net-(IC3C-OUT)") (class "Default")
      (node (ref "IC3") (pin "8") (pinfunction "OUT_8") (pintype "output"))
      (node (ref "R32") (pin "1") (pinfunction "1_1") (pintype "passive"))
    )
    (net (code "36") (name "Net-(IC3D-+IN)") (class "Default")
      (node (ref "IC3") (pin "12") (pinfunction "+IN_12") (pintype "input"))
      (node (ref "R23") (pin "1") (pinfunction "1_1") (pintype "passive"))
      (node (ref "ZD1") (pin "C") (pinfunction "C_C") (pintype "passive"))
    )
    (net (code "37") (name "Net-(IC4-+IN)") (class "Default")
      (node (ref "IC4") (pin "3") (pinfunction "+IN_3") (pintype "input"))
      (node (ref "TP23") (pin "P$1") (pinfunction "TP_P$1") (pintype "input"))
      (node (ref "VR3") (pin "P$2") (pinfunction "S_P$2") (pintype "passive"))
    )
    (net (code "38") (name "Net-(IC4--IN)") (class "Default")
      (node (ref "IC4") (pin "1") (pinfunction "OUT_1") (pintype "output"))
      (node (ref "IC4") (pin "4") (pinfunction "-IN_4") (pintype "input"))
      (node (ref "X6") (pin "P$1") (pinfunction "1_P$1") (pintype "passive"))
    )
    (net (code "39") (name "Net-(IC5-+IN)") (class "Default")
      (node (ref "IC5") (pin "3") (pinfunction "+IN_3") (pintype "input"))
      (node (ref "TP24") (pin "P$1") (pinfunction "TP_P$1") (pintype "input"))
      (node (ref "VR4") (pin "P$2") (pinfunction "S_P$2") (pintype "passive"))
    )
    (net (code "40") (name "Net-(IC5--IN)") (class "Default")
      (node (ref "IC5") (pin "1") (pinfunction "OUT_1") (pintype "output"))
      (node (ref "IC5") (pin "4") (pinfunction "-IN_4") (pintype "input"))
      (node (ref "X6") (pin "P$3") (pinfunction "3_P$3") (pintype "passive"))
    )
    (net (code "41") (name "Net-(LD1-A)") (class "Default")
      (node (ref "LD1") (pin "P$1") (pinfunction "A_P$1") (pintype "passive"))
      (node (ref "Q3") (pin "P$3") (pinfunction "C_P$3") (pintype "passive"))
      (node (ref "TP15") (pin "P$1") (pinfunction "TP_P$1") (pintype "input"))
    )
    (net (code "42") (name "Net-(LED1-PadA)") (class "Default")
      (node (ref "LED1") (pin "A") (pinfunction "A_A") (pintype "passive"))
      (node (ref "LED2") (pin "C") (pinfunction "C_C") (pintype "passive"))
      (node (ref "R9") (pin "2") (pinfunction "2_2") (pintype "passive"))
    )
    (net (code "43") (name "Net-(LED3-PadC)") (class "Default")
      (node (ref "LED3") (pin "C") (pinfunction "C_C") (pintype "passive"))
      (node (ref "LED4") (pin "A") (pinfunction "A_A") (pintype "passive"))
      (node (ref "R10") (pin "2") (pinfunction "2_2") (pintype "passive"))
    )
    (net (code "44") (name "Net-(Q1-G)") (class "Default")
      (node (ref "Q1") (pin "P$4") (pinfunction "G_P$4") (pintype "passive"))
      (node (ref "Q2") (pin "P$4") (pinfunction "G_P$4") (pintype "passive"))
      (node (ref "R32") (pin "2") (pinfunction "2_2") (pintype "passive"))
    )
    (net (code "45") (name "Net-(Q1-S-PadP$1)") (class "Default")
      (node (ref "Q1") (pin "P$1") (pinfunction "S_P$1") (pintype "passive"))
      (node (ref "Q1") (pin "P$2") (pinfunction "S_P$2") (pintype "passive"))
      (node (ref "Q1") (pin "P$3") (pinfunction "S_P$3") (pintype "passive"))
      (node (ref "Q2") (pin "P$1") (pinfunction "S_P$1") (pintype "passive"))
      (node (ref "Q2") (pin "P$2") (pinfunction "S_P$2") (pintype "passive"))
      (node (ref "Q2") (pin "P$3") (pinfunction "S_P$3") (pintype "passive"))
    )
    (net (code "46") (name "Net-(Q3-B)") (class "Default")
      (node (ref "Q3") (pin "P$1") (pinfunction "B_P$1") (pintype "passive"))
      (node (ref "R17") (pin "2") (pinfunction "2_2") (pintype "passive"))
      (node (ref "TP16") (pin "P$1") (pinfunction "TP_P$1") (pintype "input"))
      (node (ref "VR5") (pin "P$1") (pinfunction "A_P$1") (pintype "passive"))
    )
    (net (code "47") (name "Net-(Q3-E)") (class "Default")
      (node (ref "Q3") (pin "P$2") (pinfunction "E_P$2") (pintype "passive"))
      (node (ref "R15") (pin "1") (pinfunction "1_1") (pintype "passive"))
      (node (ref "TP13") (pin "P$1") (pinfunction "TP_P$1") (pintype "input"))
    )
    (net (code "48") (name "Net-(Q4-C)") (class "Default")
      (node (ref "Q4") (pin "P$3") (pinfunction "C_P$3") (pintype "input"))
      (node (ref "R17") (pin "1") (pinfunction "1_1") (pintype "passive"))
    )
    (net (code "49") (name "Net-(R34-Pad1)") (class "Default")
      (node (ref "R34") (pin "1") (pinfunction "1_1") (pintype "passive"))
      (node (ref "VR1") (pin "S") (pinfunction "S_S") (pintype "passive"))
    )
    (net (code "50") (name "Net-(R36-Pad2)") (class "Default")
      (node (ref "R36") (pin "2") (pinfunction "2_2") (pintype "passive"))
      (node (ref "VR2") (pin "S") (pinfunction "S_S") (pintype "passive"))
    )
    (net (code "51") (name "Net-(TP19-TP)") (class "Default")
      (node (ref "D3") (pin "A") (pinfunction "A_A") (pintype "passive"))
      (node (ref "L1") (pin "2") (pinfunction "2_2") (pintype "passive"))
      (node (ref "TP19") (pin "P$1") (pinfunction "TP_P$1") (pintype "input"))
      (node (ref "U1") (pin "P5") (pinfunction "SW_P5") (pintype "bidirectional"))
    )
    (net (code "52") (name "Net-(TP20-TP)") (class "Default")
      (node (ref "CBST-NEG") (pin "2") (pinfunction "2_2") (pintype "passive"))
      (node (ref "D1-NEG") (pin "C") (pinfunction "C_C") (pintype "passive"))
      (node (ref "L1-NEG") (pin "1") (pinfunction "1_1") (pintype "passive"))
      (node (ref "TP20") (pin "P$1") (pinfunction "TP_P$1") (pintype "input"))
      (node (ref "U2") (pin "6") (pinfunction "SW_6") (pintype "bidirectional"))
    )
    (net (code "53") (name "Net-(TP21-TP)") (class "Default")
      (node (ref "C2") (pin "2") (pinfunction "2_2") (pintype "passive"))
      (node (ref "JP2") (pin "2") (pinfunction "2_2") (pintype "passive"))
      (node (ref "TP21") (pin "P$1") (pinfunction "TP_P$1") (pintype "input"))
      (node (ref "VR1") (pin "E") (pinfunction "E_E") (pintype "passive"))
    )
    (net (code "54") (name "Net-(TP22-TP)") (class "Default")
      (node (ref "C3") (pin "2") (pinfunction "2_2") (pintype "passive"))
      (node (ref "JP3") (pin "1") (pinfunction "1_1") (pintype "passive"))
      (node (ref "TP22") (pin "P$1") (pinfunction "TP_P$1") (pintype "input"))
      (node (ref "VR2") (pin "E") (pinfunction "E_E") (pintype "passive"))
    )
    (net (code "55") (name "Net-(U1-COMP)") (class "Default")
      (node (ref "CC1") (pin "1") (pinfunction "1_1") (pintype "passive"))
      (node (ref "CC2") (pin "1") (pinfunction "1_1") (pintype "passive"))
      (node (ref "U1") (pin "P1") (pinfunction "COMP_P1") (pintype "bidirectional"))
    )
    (net (code "56") (name "Net-(U1-EN)") (class "Default")
      (node (ref "REN") (pin "1") (pinfunction "1_1") (pintype "passive"))
      (node (ref "U1") (pin "P3") (pinfunction "EN_P3") (pintype "bidirectional"))
    )
    (net (code "57") (name "Net-(U1-FB)") (class "Default")
      (node (ref "RF1") (pin "1") (pinfunction "1_1") (pintype "passive"))
      (node (ref "RF2") (pin "2") (pinfunction "2_2") (pintype "passive"))
      (node (ref "U1") (pin "P2") (pinfunction "FB_P2") (pintype "bidirectional"))
    )
    (net (code "58") (name "Net-(U1-SS)") (class "Default")
      (node (ref "CSS") (pin "1") (pinfunction "1_1") (pintype "passive"))
      (node (ref "U1") (pin "P8") (pinfunction "SS_P8") (pintype "bidirectional"))
    )
    (net (code "59") (name "Net-(U1-VIN)") (class "Default")
      (node (ref "CV5") (pin "1") (pinfunction "1_1") (pintype "passive"))
      (node (ref "RB0") (pin "1") (pinfunction "1_1") (pintype "passive"))
      (node (ref "REN") (pin "2") (pinfunction "2_2") (pintype "passive"))
      (node (ref "U1") (pin "P6") (pinfunction "VIN_P6") (pintype "bidirectional"))
    )
    (net (code "60") (name "Net-(U2-BST)") (class "Default")
      (node (ref "CBST-NEG") (pin "1") (pinfunction "1_1") (pintype "passive"))
      (node (ref "U2") (pin "1") (pinfunction "BST_1") (pintype "bidirectional"))
    )
    (net (code "61") (name "Net-(U2-FB)") (class "Default")
      (node (ref "RF1-NEG") (pin "1") (pinfunction "1_1") (pintype "passive"))
      (node (ref "RF2-NEG") (pin "1") (pinfunction "1_1") (pintype "passive"))
      (node (ref "U2") (pin "3") (pinfunction "FB_3") (pintype "input"))
    )
    (net (code "62") (name "Net-(VR3-E)") (class "Default")
      (node (ref "VR3") (pin "P$3") (pinfunction "E_P$3") (pintype "passive"))
      (node (ref "X2") (pin "2") (pinfunction "2_2") (pintype "passive"))
    )
    (net (code "63") (name "Net-(VR4-E)") (class "Default")
      (node (ref "VR4") (pin "P$3") (pinfunction "E_P$3") (pintype "passive"))
      (node (ref "X3") (pin "2") (pinfunction "2_2") (pintype "passive"))
    )
    (net (code "64") (name "Net-(VR5-E)") (class "Default")
      (node (ref "R16") (pin "1") (pinfunction "1_1") (pintype "passive"))
      (node (ref "VR5") (pin "P$2") (pinfunction "S_P$2") (pintype "passive"))
      (node (ref "VR5") (pin "P$3") (pinfunction "E_P$3") (pintype "passive"))
    )
    (net (code "65") (name "TOMIC") (class "Default")
      (node (ref "CON2") (pin "P$2") (pinfunction "3_P$2") (pintype "passive"))
      (node (ref "R29") (pin "1") (pinfunction "1_1") (pintype "passive"))
      (node (ref "R33") (pin "2") (pinfunction "2_2") (pintype "passive"))
    )
    (net (code "66") (name "TP5") (class "Default")
      (node (ref "IC1") (pin "8") (pinfunction "OUT_8") (pintype "output"))
      (node (ref "IC2") (pin "2") (pinfunction "-IN_2") (pintype "input"))
      (node (ref "R24") (pin "2") (pinfunction "2_2") (pintype "passive"))
      (node (ref "TP5") (pin "P$1") (pinfunction "TP_P$1") (pintype "input"))
      (node (ref "X2") (pin "1") (pinfunction "1_1") (pintype "passive"))
    )
    (net (code "67") (name "TP6") (class "Default")
      (node (ref "IC1") (pin "7") (pinfunction "OUT_7") (pintype "output"))
      (node (ref "IC2") (pin "6") (pinfunction "-IN_6") (pintype "input"))
      (node (ref "R25") (pin "2") (pinfunction "2_2") (pintype "passive"))
      (node (ref "TP6") (pin "P$1") (pinfunction "TP_P$1") (pintype "input"))
      (node (ref "X3") (pin "1") (pinfunction "1_1") (pintype "passive"))
    )
    (net (code "68") (name "USB5V") (class "Default")
      (node (ref "CC-NEG") (pin "1") (pinfunction "1_1") (pintype "passive"))
      (node (ref "CIN") (pin "1") (pinfunction "1_1") (pintype "passive"))
      (node (ref "CIN-NEG") (pin "1") (pinfunction "1_1") (pintype "passive"))
      (node (ref "L1") (pin "1") (pinfunction "1_1") (pintype "passive"))
      (node (ref "RB0") (pin "2") (pinfunction "2_2") (pintype "passive"))
      (node (ref "TP7") (pin "P$1") (pinfunction "TP_P$1") (pintype "input"))
      (node (ref "U2") (pin "4") (pinfunction "EN_4") (pintype "input"))
      (node (ref "U2") (pin "5") (pinfunction "VIN_5") (pintype "power_in"))
      (node (ref "USB2") (pin "P$1") (pinfunction "1_P$1") (pintype "input"))
    )
    (net (code "69") (name "V+") (class "Default")
      (node (ref "COUT1") (pin "1") (pinfunction "1_1") (pintype "passive"))
      (node (ref "D3") (pin "C") (pinfunction "C_C") (pintype "passive"))
      (node (ref "IC1") (pin "4") (pinfunction "V+_4") (pintype "power_in"))
      (node (ref "IC2") (pin "4") (pinfunction "V+_4") (pintype "power_in"))
      (node (ref "IC3") (pin "4") (pinfunction "V+_4") (pintype "power_in"))
      (node (ref "IC4") (pin "2") (pinfunction "V+_2") (pintype "power_in"))
      (node (ref "IC5") (pin "2") (pinfunction "V+_2") (pintype "power_in"))
      (node (ref "R15") (pin "2") (pinfunction "2_2") (pintype "passive"))
      (node (ref "R16") (pin "2") (pinfunction "2_2") (pintype "passive"))
      (node (ref "R23") (pin "2") (pinfunction "2_2") (pintype "passive"))
      (node (ref "RF1") (pin "2") (pinfunction "2_2") (pintype "passive"))
      (node (ref "TP10") (pin "P$1") (pinfunction "TP_P$1") (pintype "input"))
      (node (ref "X7") (pin "3") (pinfunction "1_3") (pintype "passive"))
      (node (ref "X9") (pin "1") (pinfunction "1_1") (pintype "passive"))
    )
    (net (code "70") (name "V-") (class "Default")
      (node (ref "CC-NEG") (pin "2") (pinfunction "2_2") (pintype "passive"))
      (node (ref "COUT1-NEG") (pin "2") (pinfunction "2_2") (pintype "passive"))
      (node (ref "D1-NEG") (pin "A") (pinfunction "A_A") (pintype "passive"))
      (node (ref "IC1") (pin "11") (pinfunction "V-_11") (pintype "power_in"))
      (node (ref "IC2") (pin "11") (pinfunction "V-_11") (pintype "power_in"))
      (node (ref "IC3") (pin "11") (pinfunction "V-_11") (pintype "power_in"))
      (node (ref "IC4") (pin "5") (pinfunction "V-_5") (pintype "power_in"))
      (node (ref "IC5") (pin "5") (pinfunction "V-_5") (pintype "power_in"))
      (node (ref "RF2-NEG") (pin "2") (pinfunction "2_2") (pintype "passive"))
      (node (ref "TP11") (pin "P$1") (pinfunction "TP_P$1") (pintype "input"))
      (node (ref "U2") (pin "2") (pinfunction "AGND_2") (pintype "power_in"))
      (node (ref "X9") (pin "3") (pinfunction "1_3") (pintype "passive"))
    )
    (net (code "71") (name "unconnected-(CON2-2-PadP$3)") (class "Default")
      (node (ref "CON2") (pin "P$3") (pinfunction "2_P$3") (pintype "passive"))
    )
    (net (code "72") (name "unconnected-(USB2A-2-PadP$2)") (class "Default")
      (node (ref "USB2") (pin "P$2") (pinfunction "2_P$2") (pintype "input"))
    )
    (net (code "73") (name "unconnected-(USB2A-3-PadP$3)") (class "Default")
      (node (ref "USB2") (pin "P$3") (pinfunction "3_P$3") (pintype "input"))
    )
    (net (code "74") (name "unconnected-(USB2A-4-PadP$4)") (class "Default")
      (node (ref "USB2") (pin "P$4") (pinfunction "4_P$4") (pintype "input"))
    )
  )
)
